# XCZU_LED_STATUS.net
KiCad netlist of a schematic drawn in Altium Designer
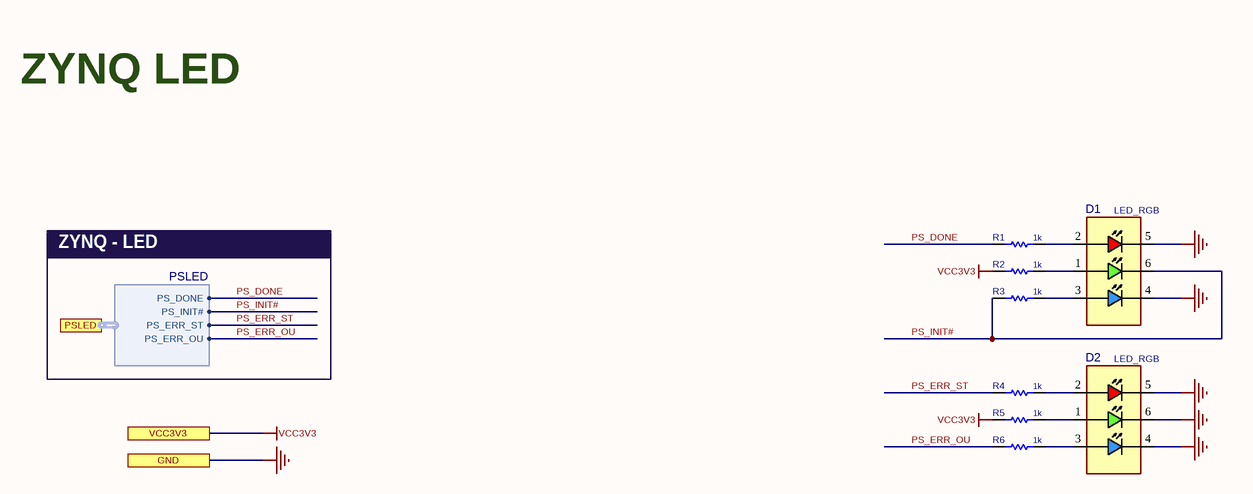
[diagram p0: XCZU_LED_STATUS.SchDoc]

(export (version "E")
  (design (tool "Eeschema 10.0.6"))
  (components
    (comp (ref "D1")
      (value "LED_RGB")
      (footprint "LED1615RGB")
      (description "LED, SMD, RGB")
      (fields (field (name "MANF_P#") "E6C1615RGBC3UDA") (field (name "MANF") "EKINGLUX"))
      (libsource (lib "led(diode)") (part "LED_SMD_RGB_E6C1615"))
    )
    (comp (ref "D2")
      (value "LED_RGB")
      (footprint "LED1615RGB")
      (description "LED, SMD, RGB")
      (fields (field (name "MANF_P#") "E6C1615RGBC3UDA") (field (name "MANF") "EKINGLUX"))
      (libsource (lib "led(diode)") (part "LED_SMD_RGB_E6C1615"))
    )
    (comp (ref "R1")
      (value "1k")
      (footprint "R0402")
      (description "RESISTOR, SMD")
      (libsource (lib "passive_smd") (part "RES_SMD"))
    )
    (comp (ref "R2")
      (value "1k")
      (footprint "R0402")
      (description "RESISTOR, SMD")
      (libsource (lib "passive_smd") (part "RES_SMD"))
    )
    (comp (ref "R3")
      (value "1k")
      (footprint "R0402")
      (description "RESISTOR, SMD")
      (libsource (lib "passive_smd") (part "RES_SMD"))
    )
    (comp (ref "R4")
      (value "1k")
      (footprint "R0402")
      (description "RESISTOR, SMD")
      (libsource (lib "passive_smd") (part "RES_SMD"))
    )
    (comp (ref "R5")
      (value "1k")
      (footprint "R0402")
      (description "RESISTOR, SMD")
      (libsource (lib "passive_smd") (part "RES_SMD"))
    )
    (comp (ref "R6")
      (value "1k")
      (footprint "R0402")
      (description "RESISTOR, SMD")
      (libsource (lib "passive_smd") (part "RES_SMD"))
    )
  )
  (nets
    (net (code "2") (name "/PS_DONE") (class "Default")
      (node (ref "R1") (pin "1") (pinfunction "1_1") (pintype "passive"))
    )
    (net (code "3") (name "/PS_ERR_OU") (class "Default")
      (node (ref "R6") (pin "1") (pinfunction "1_1") (pintype "passive"))
    )
    (net (code "4") (name "/PS_ERR_ST") (class "Default")
      (node (ref "R4") (pin "1") (pinfunction "1_1") (pintype "passive"))
    )
    (net (code "5") (name "/PS_INIT#") (class "Default")
      (node (ref "D1") (pin "6") (pinfunction "K_GRN_6") (pintype "passive"))
      (node (ref "R3") (pin "1") (pinfunction "1_1") (pintype "passive"))
    )
    (net (code "7") (name "GND") (class "Default")
      (node (ref "D1") (pin "4") (pinfunction "K_BLU_4") (pintype "passive"))
      (node (ref "D1") (pin "5") (pinfunction "K_RED_5") (pintype "passive"))
      (node (ref "D2") (pin "4") (pinfunction "K_BLU_4") (pintype "passive"))
      (node (ref "D2") (pin "5") (pinfunction "K_RED_5") (pintype "passive"))
      (node (ref "D2") (pin "6") (pinfunction "K_GRN_6") (pintype "passive"))
    )
    (net (code "8") (name "Net-(D1-A_BLU)") (class "Default")
      (node (ref "D1") (pin "3") (pinfunction "A_BLU_3") (pintype "passive"))
      (node (ref "R3") (pin "2") (pinfunction "2_2") (pintype "passive"))
    )
    (net (code "9") (name "Net-(D1-A_GRN)") (class "Default")
      (node (ref "D1") (pin "1") (pinfunction "A_GRN_1") (pintype "passive"))
      (node (ref "R2") (pin "2") (pinfunction "2_2") (pintype "passive"))
    )
    (net (code "10") (name "Net-(D1-A_RED)") (class "Default")
      (node (ref "D1") (pin "2") (pinfunction "A_RED_2") (pintype "passive"))
      (node (ref "R1") (pin "2") (pinfunction "2_2") (pintype "passive"))
    )
    (net (code "11") (name "Net-(D2-A_BLU)") (class "Default")
      (node (ref "D2") (pin "3") (pinfunction "A_BLU_3") (pintype "passive"))
      (node (ref "R6") (pin "2") (pinfunction "2_2") (pintype "passive"))
    )
    (net (code "12") (name "Net-(D2-A_GRN)") (class "Default")
      (node (ref "D2") (pin "1") (pinfunction "A_GRN_1") (pintype "passive"))
      (node (ref "R5") (pin "2") (pinfunction "2_2") (pintype "passive"))
    )
    (net (code "13") (name "Net-(D2-A_RED)") (class "Default")
      (node (ref "D2") (pin "2") (pinfunction "A_RED_2") (pintype "passive"))
      (node (ref "R4") (pin "2") (pinfunction "2_2") (pintype "passive"))
    )
    (net (code "14") (name "VCC3V3") (class "Default")
      (node (ref "R2") (pin "1") (pinfunction "1_1") (pintype "passive"))
      (node (ref "R5") (pin "1") (pinfunction "1_1") (pintype "passive"))
    )
  )
)
